# DLY-056.net
KiCad netlist of a schematic drawn in Altium Designer
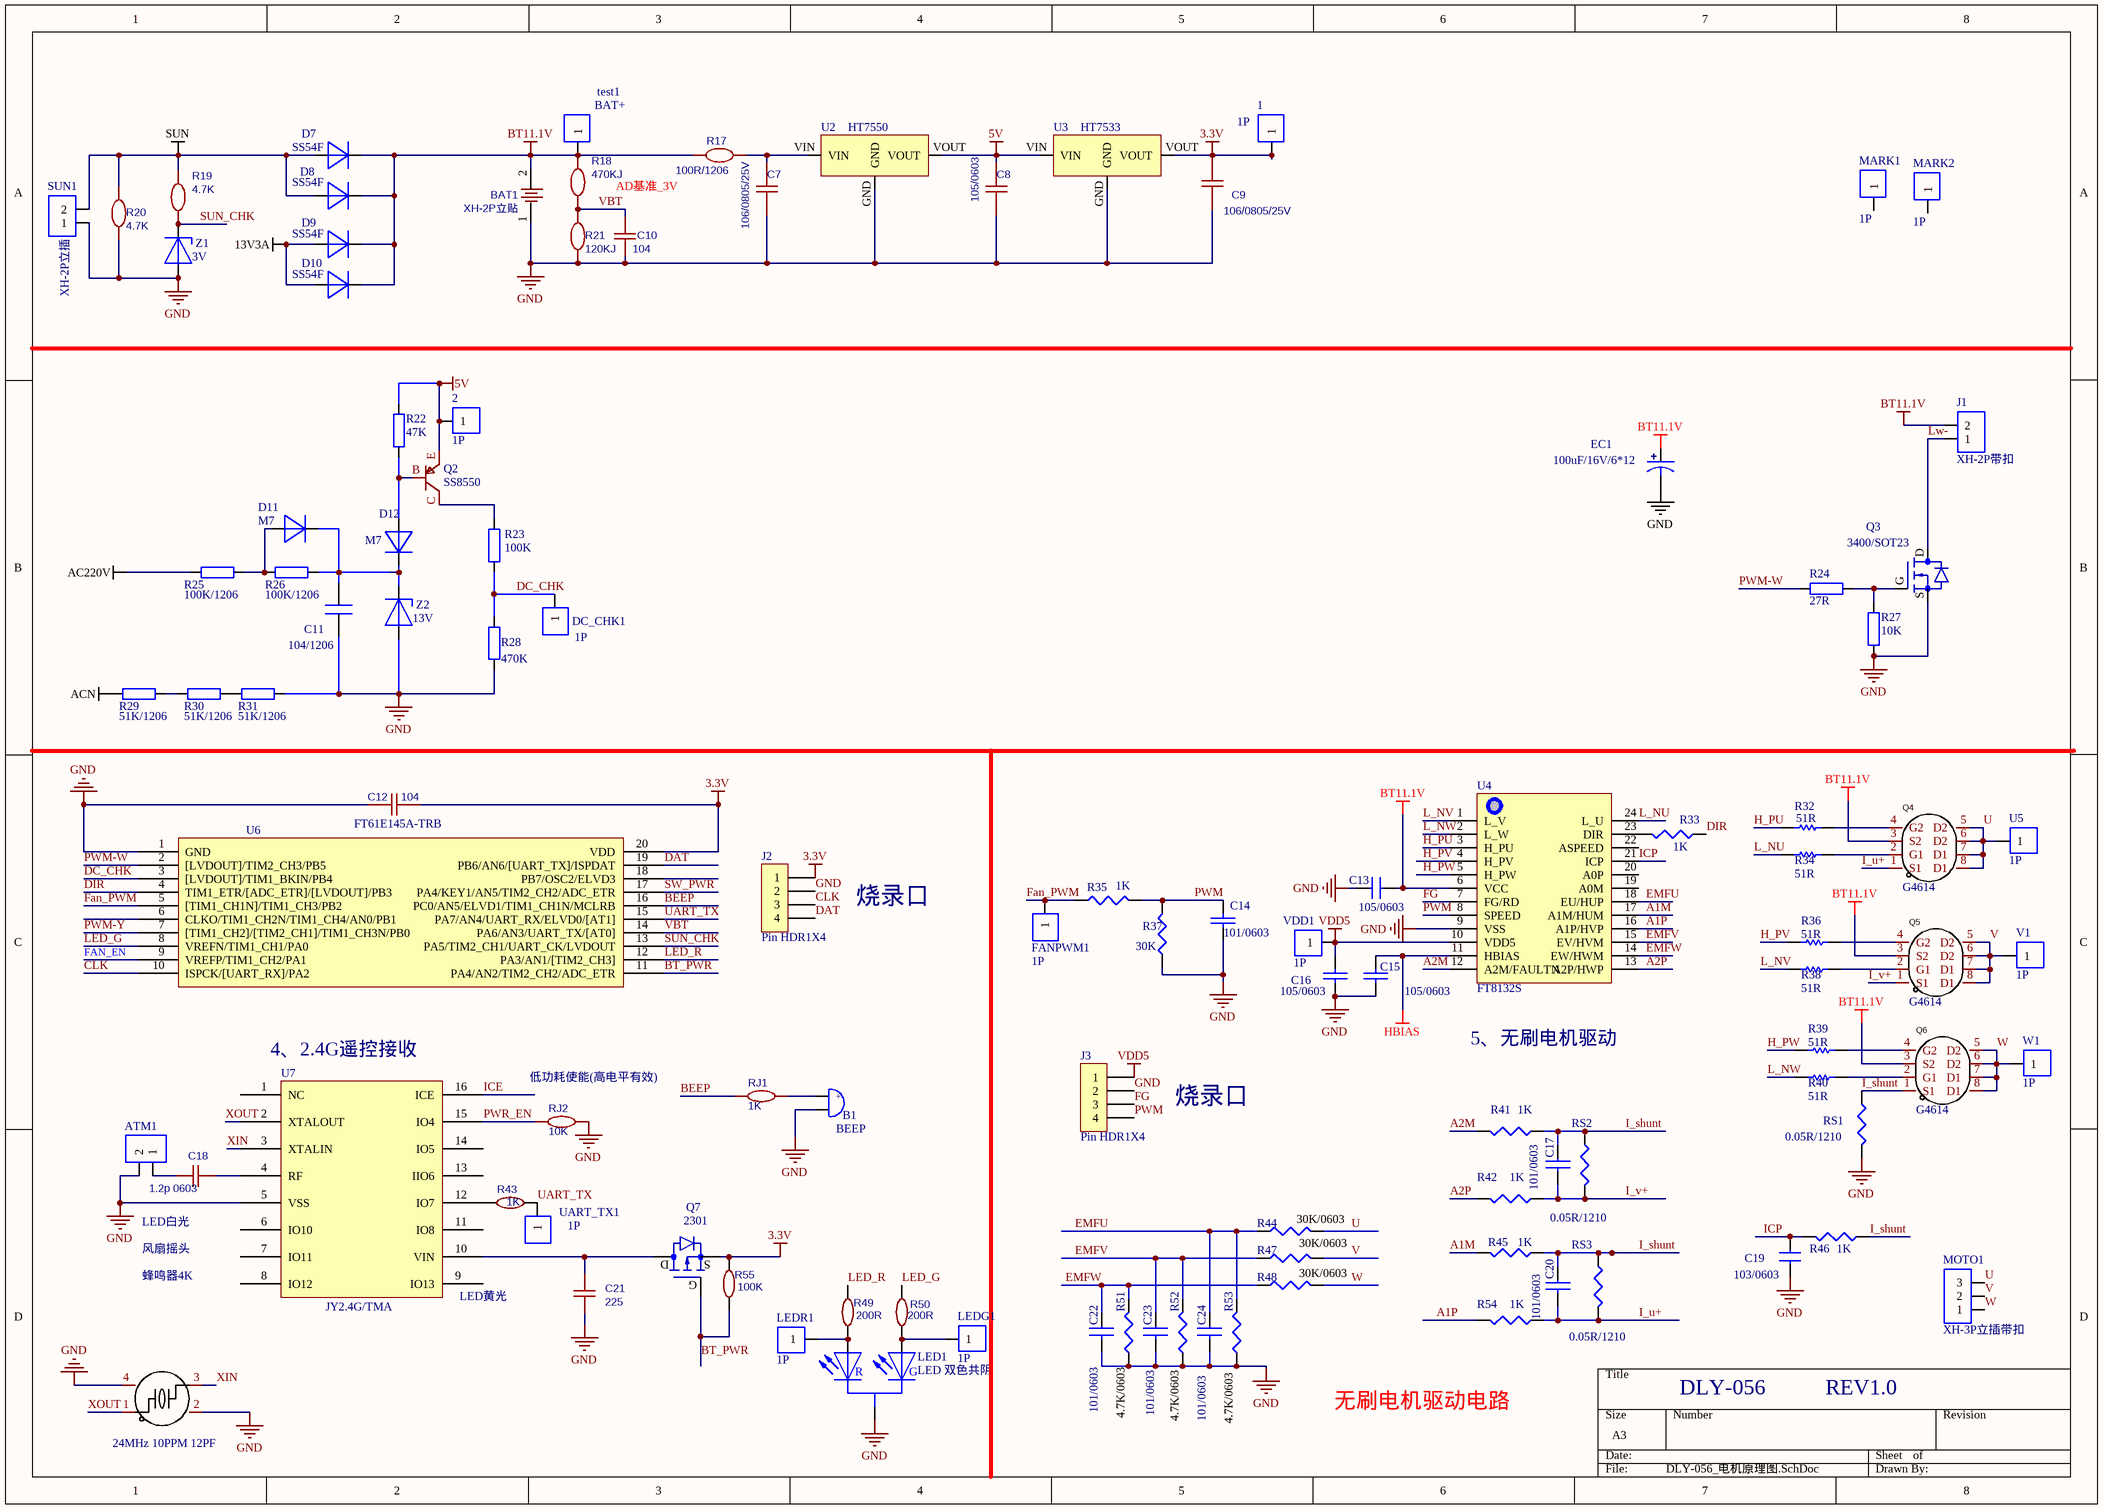
[diagram p0: DLY-056_电机原理图.SchDoc]

(export (version "E")
  (design (tool "Eeschema 10.0.6"))
  (components
    (comp (ref "1")
      (value "1P")
      (footprint "TEST3.0_top")
      (libsource (lib "KENNED 原理图标准封装-2023-9-7") (part "1P"))
    )
    (comp (ref "2")
      (value "1P")
      (footprint "TEST3.0_top")
      (libsource (lib "KENNED 原理图标准封装-2023-9-7") (part "1P"))
    )
    (comp (ref "ATM1")
      (value "2P")
      (footprint "SMT-ATN天线")
      (libsource (lib "KENNED 原理图标准封装-2023-9-7") (part "2P"))
    )
    (comp (ref "B1")
      (value "BEEP")
      (footprint "MI-蜂鸣器-1407")
      (description "蜂鸣器")
      (libsource (lib "蜂鸣器") (part "BEEP"))
    )
    (comp (ref "BAT1")
      (value "XH-2P立贴")
      (footprint "MI-VH2-2.5")
      (fields (field (name "BOM_MANUFACTURER PART") "CR1220-2") (field (name "BOM_SUPPLIER PART") "C70381"))
      (libsource (lib "altium-import") (part "root_3_12V_"))
    )
    (comp (ref "C7")
      (value "106/0805/25V")
      (footprint "0805_c")
      (fields (field (name "CONTRIBUTOR") "LCEDA_Lib"))
      (libsource (lib "altium-import") (part "root_3_0.1u_"))
    )
    (comp (ref "C8")
      (value "105/0603")
      (footprint "0603_c")
      (fields (field (name "CONTRIBUTOR") "LCEDA_Lib"))
      (libsource (lib "altium-import") (part "root_3_0.1u_"))
    )
    (comp (ref "C9")
      (value "106/0805/25V")
      (footprint "0603_c")
      (fields (field (name "CONTRIBUTOR") "LCEDA_Lib"))
      (libsource (lib "altium-import") (part "root_3_0.1u_"))
    )
    (comp (ref "C10")
      (value "104")
      (footprint "0603_C")
      (fields
        (field (name "BOM_SUPPLIER PART") "C295939")
        (field (name "BOM_MANUFACTURER PART") "0402X224J100CT")
        (field (name "CONTRIBUTOR") "LCSC")
      )
      (libsource (lib "altium-import") (part "root_0_100nF_"))
    )
    (comp (ref "C11")
      (value "104/1206")
      (footprint "1206_C")
      (libsource (lib "KENNED 原理图标准封装-20170515") (part "Cap"))
    )
    (comp (ref "C12")
      (value "104")
      (footprint "0603_C")
      (fields
        (field (name "BOM_MANUFACTURER PART") "CL10B104KA8NNNC")
        (field (name "BOM_SUPPLIER PART") "C1590")
      )
      (libsource (lib "altium-import") (part "root_2_102/400V_"))
    )
    (comp (ref "C13")
      (value "105/0603")
      (footprint "0603_C")
      (description "Capacitor")
      (libsource (lib "*") (part "CAP"))
    )
    (comp (ref "C14")
      (value "101/0603")
      (footprint "0603_C")
      (description "Capacitor")
      (libsource (lib "") (part "CAP_1"))
    )
    (comp (ref "C15")
      (value "105/0603")
      (footprint "0603_C")
      (description "Capacitor")
      (libsource (lib "*") (part "CAP-CC"))
    )
    (comp (ref "C16")
      (value "105/0603")
      (footprint "0603_C")
      (description "Capacitor")
      (libsource (lib "*") (part "CAP-CC"))
    )
    (comp (ref "C17") (value "101/0603") (footprint "0603_C") (libsource (lib "*") (part "CAP NP")))
    (comp (ref "C18")
      (value "1.2p 0603")
      (footprint "0603_C")
      (description "0603")
      (fields
        (field (name "BOM_SUPPLIER PART") "C295939")
        (field (name "BOM_MANUFACTURER PART") "0402X224J100CT")
        (field (name "CONTRIBUTOR") "LCSC")
      )
      (libsource (lib "altium-import") (part "root_3_100nF_"))
    )
    (comp (ref "C19")
      (value "103/0603")
      (footprint "0603_C")
      (description "Capacitor")
      (libsource (lib "*") (part "CAP"))
    )
    (comp (ref "C20") (value "101/0603") (footprint "0603_C") (libsource (lib "*") (part "CAP NP")))
    (comp (ref "C21")
      (value "225")
      (footprint "0603_C")
      (description "0603")
      (fields
        (field (name "BOM_SUPPLIER PART") "C295939")
        (field (name "BOM_MANUFACTURER PART") "0402X224J100CT")
        (field (name "CONTRIBUTOR") "LCSC")
      )
      (libsource (lib "altium-import") (part "root_2_100nF_"))
    )
    (comp (ref "C22") (value "101/0603") (footprint "0603_C") (libsource (lib "*") (part "CAP NP")))
    (comp (ref "C23") (value "101/0603") (footprint "0603_C") (libsource (lib "*") (part "CAP NP")))
    (comp (ref "C24") (value "101/0603") (footprint "0603_C") (libsource (lib "*") (part "CAP NP")))
    (comp (ref "D7")
      (value "SS54F")
      (footprint "SMT-SMA")
      (libsource (lib "KENNED 原理图标准封装-20170515") (part "Diode"))
    )
    (comp (ref "D8")
      (value "SS54F")
      (footprint "SMT-SMA")
      (libsource (lib "KENNED 原理图标准封装-20170515") (part "Diode"))
    )
    (comp (ref "D9")
      (value "SS54F")
      (footprint "SMT-SMA")
      (libsource (lib "KENNED 原理图标准封装-20170515") (part "Diode"))
    )
    (comp (ref "D10")
      (value "SS54F")
      (footprint "SMT-SMA")
      (libsource (lib "KENNED 原理图标准封装-20170515") (part "Diode"))
    )
    (comp (ref "D11")
      (value "M7")
      (footprint "SMT-SOD123锡膏")
      (libsource (lib "KENNED 原理图标准封装-20170515") (part "Diode"))
    )
    (comp (ref "D12")
      (value "M7")
      (footprint "SMT-SOD123锡膏")
      (libsource (lib "KENNED 原理图标准封装-20170515") (part "Diode"))
    )
    (comp (ref "DC_CHK1")
      (value "1P")
      (footprint "TEST3.0_top")
      (libsource (lib "KENNED 原理图标准封装-2023-9-7") (part "1P"))
    )
    (comp (ref "EC1")
      (value "100uF/16V/6*12")
      (footprint "DIP-EC2.5X6.3X11.2")
      (description "贴片电解电容")
      (libsource (lib "电容") (part "SMD_ECAP"))
    )
    (comp (ref "FANPWM1")
      (value "1P")
      (footprint "TEST3.0_top")
      (libsource (lib "KENNED 原理图标准封装-2023-9-7") (part "1P"))
    )
    (comp (ref "J1")
      (value "XH-2P带扣")
      (footprint "MI-VH2-2.5")
      (libsource (lib "KENNED 原理图标准封装-2023-9-7") (part "2P"))
    )
    (comp (ref "J2") (value "Pin HDR1X4") (footprint "烧录口") (libsource (lib "排针") (part "Pin HDR1X4")))
    (comp (ref "J3") (value "Pin HDR1X4") (footprint "烧录口") (libsource (lib "排针") (part "Pin HDR1X4")))
    (comp (ref "LED1")
      (value "LED 双色共阴")
      (footprint "PH2.0-3P")
      (libsource (lib "KENNED 原理图标准封装-2023-9-7") (part "LED 双色共阴"))
    )
    (comp (ref "LEDG1")
      (value "1P")
      (footprint "TEST3.0_top")
      (libsource (lib "KENNED 原理图标准封装-2023-9-7") (part "1P"))
    )
    (comp (ref "LEDR1")
      (value "1P")
      (footprint "TEST3.0_top")
      (libsource (lib "KENNED 原理图标准封装-2023-9-7") (part "1P"))
    )
    (comp (ref "MARK1")
      (value "1P")
      (footprint "SMT-MARK")
      (libsource (lib "KENNED 原理图标准封装-2023-9-7") (part "1P"))
    )
    (comp (ref "MARK2")
      (value "1P")
      (footprint "SMT-MARK")
      (libsource (lib "KENNED 原理图标准封装-2023-9-7") (part "1P"))
    )
    (comp (ref "MOTO1")
      (value "XH-3P立插带扣")
      (footprint "MI-VH3-2.5")
      (libsource (lib "KENNED 原理图标准封装-2023-9-7") (part "3P"))
    )
    (comp (ref "Q2")
      (value "SS8550")
      (footprint "SMT-三极管-SOT23锡膏")
      (libsource (lib "KENNED 原理图标准封装-2023-9-7") (part "PNP"))
    )
    (comp (ref "Q3")
      (value "3400/SOT23")
      (footprint "SMT-MOS管-SOT23锡膏")
      (libsource (lib "KENNED 原理图标准封装-2023-9-7") (part "N MOS"))
    )
    (comp (ref "Q4")
      (value "G4614")
      (footprint "SOIC-8_150mil")
      (libsource (lib "altium-import") (part "root_2_mirrored_G4614_"))
    )
    (comp (ref "Q5")
      (value "G4614")
      (footprint "SOIC-8_150mil")
      (libsource (lib "altium-import") (part "root_2_mirrored_G4614_"))
    )
    (comp (ref "Q6")
      (value "G4614")
      (footprint "SOIC-8_150mil")
      (libsource (lib "altium-import") (part "root_2_mirrored_G4614_"))
    )
    (comp (ref "Q7")
      (value "2301")
      (footprint "SMT-MOS管-SOT23锡膏")
      (libsource (lib "KENNED 原理图标准封装-2023-9-7") (part "P MOS"))
    )
    (comp (ref "R17")
      (value "100R/1206")
      (footprint "SMT-1206r")
      (fields (field (name "CONTRIBUTOR") "LCEDA_Lib"))
      (libsource (lib "altium-import") (part "root_2_1k_"))
    )
    (comp (ref "R18")
      (value "470KJ")
      (footprint "0603_R")
      (fields (field (name "CONTRIBUTOR") "LCEDA_Lib"))
      (libsource (lib "altium-import") (part "root_1_1k_"))
    )
    (comp (ref "R19")
      (value "4.7K")
      (footprint "0603_R")
      (fields (field (name "CONTRIBUTOR") "LCEDA_Lib"))
      (libsource (lib "altium-import") (part "root_1_1k_"))
    )
    (comp (ref "R20")
      (value "4.7K")
      (footprint "0603_R")
      (fields (field (name "CONTRIBUTOR") "LCEDA_Lib"))
      (libsource (lib "altium-import") (part "root_1_1k_"))
    )
    (comp (ref "R21")
      (value "120KJ")
      (footprint "0603_R")
      (fields (field (name "CONTRIBUTOR") "LCEDA_Lib"))
      (libsource (lib "altium-import") (part "root_1_1k_"))
    )
    (comp (ref "R22")
      (value "47K")
      (footprint "SMT-0603R")
      (libsource (lib "KENNED 原理图标准封装-20170515") (part "Res"))
    )
    (comp (ref "R23")
      (value "100K")
      (footprint "SMT-0603R")
      (libsource (lib "KENNED 原理图标准封装-20170515") (part "Res"))
    )
    (comp (ref "R24") (value "27R") (footprint "SMT-0603R") (libsource (lib "*") (part "Res")))
    (comp (ref "R25")
      (value "100K/1206")
      (footprint "SMT-1206")
      (libsource (lib "KENNED 原理图标准封装-20170515") (part "Res"))
    )
    (comp (ref "R26")
      (value "100K/1206")
      (footprint "SMT-1206")
      (libsource (lib "KENNED 原理图标准封装-20170515") (part "Res"))
    )
    (comp (ref "R27") (value "10K") (footprint "SMT-0603R") (libsource (lib "*") (part "Res")))
    (comp (ref "R28")
      (value "470K")
      (footprint "SMT-0603R")
      (libsource (lib "KENNED 原理图标准封装-20170515") (part "Res"))
    )
    (comp (ref "R29")
      (value "51K/1206")
      (footprint "SMT-1206")
      (libsource (lib "KENNED 原理图标准封装-20170515") (part "Res"))
    )
    (comp (ref "R30")
      (value "51K/1206")
      (footprint "SMT-1206")
      (libsource (lib "KENNED 原理图标准封装-20170515") (part "Res"))
    )
    (comp (ref "R31")
      (value "51K/1206")
      (footprint "SMT-1206")
      (libsource (lib "KENNED 原理图标准封装-20170515") (part "Res"))
    )
    (comp (ref "R32") (value "51R") (footprint "SMT-0603R") (libsource (lib "*") (part "RES")))
    (comp (ref "R33") (value "1K") (footprint "SMT-0603R") (libsource (lib "*") (part "RES(SMD)")))
    (comp (ref "R34") (value "51R") (footprint "SMT-0603R") (libsource (lib "*") (part "RES")))
    (comp (ref "R35") (value "1K") (footprint "SMT-0603R") (libsource (lib "*") (part "RES(SMD)")))
    (comp (ref "R36") (value "51R") (footprint "SMT-0603R") (libsource (lib "*") (part "RES")))
    (comp (ref "R37") (value "30K") (footprint "SMT-0603R") (libsource (lib "*") (part "RES(SMD)")))
    (comp (ref "R38") (value "51R") (footprint "SMT-0603R") (libsource (lib "*") (part "RES")))
    (comp (ref "R39") (value "51R") (footprint "SMT-0603R") (libsource (lib "*") (part "RES")))
    (comp (ref "R40") (value "51R") (footprint "SMT-0603R") (libsource (lib "*") (part "RES")))
    (comp (ref "R41") (value "1K") (footprint "SMT-0603R") (libsource (lib "*") (part "RES(SMD)")))
    (comp (ref "R42") (value "1K") (footprint "SMT-0603R") (libsource (lib "*") (part "RES(SMD)")))
    (comp (ref "R43")
      (value "1K")
      (footprint "SMT-0603R")
      (fields
        (field (name "BOM_MANUFACTURER PART") "0402WGJ0165TCE")
        (field (name "BOM_SUPPLIER PART") "C57065")
      )
      (libsource (lib "altium-import") (part "root_2_51K_"))
    )
    (comp (ref "R44") (value "30K/0603") (footprint "SMT-0603R") (libsource (lib "") (part "RES(SMD)_1")))
    (comp (ref "R45") (value "1K") (footprint "SMT-0603R") (libsource (lib "*") (part "RES(SMD)")))
    (comp (ref "R46") (value "1K") (footprint "SMT-0603R") (libsource (lib "*") (part "RES(SMD)")))
    (comp (ref "R47") (value "30K/0603") (footprint "SMT-0603R") (libsource (lib "") (part "RES(SMD)_1")))
    (comp (ref "R48") (value "30K/0603") (footprint "SMT-0603R") (libsource (lib "") (part "RES(SMD)_1")))
    (comp (ref "R49")
      (value "200R")
      (footprint "SMT-0603R")
      (fields
        (field (name "BOM_MANUFACTURER PART") "0402WGJ0165TCE")
        (field (name "BOM_SUPPLIER PART") "C57065")
      )
      (libsource (lib "altium-import") (part "root_3_51K_"))
    )
    (comp (ref "R50")
      (value "200R")
      (footprint "SMT-0603R")
      (fields
        (field (name "BOM_MANUFACTURER PART") "0402WGJ0165TCE")
        (field (name "BOM_SUPPLIER PART") "C57065")
      )
      (libsource (lib "altium-import") (part "root_3_51K_"))
    )
    (comp (ref "R51") (value "4.7K/0603") (footprint "SMT-0603R") (libsource (lib "") (part "RES(SMD)_1")))
    (comp (ref "R52") (value "4.7K/0603") (footprint "SMT-0603R") (libsource (lib "") (part "RES(SMD)_1")))
    (comp (ref "R53") (value "4.7K/0603") (footprint "SMT-0603R") (libsource (lib "") (part "RES(SMD)_1")))
    (comp (ref "R54") (value "1K") (footprint "SMT-0603R") (libsource (lib "*") (part "RES(SMD)")))
    (comp (ref "R55")
      (value "100K")
      (footprint "SMT-0603R")
      (fields
        (field (name "BOM_MANUFACTURER PART") "0402WGJ0165TCE")
        (field (name "BOM_SUPPLIER PART") "C57065")
      )
      (libsource (lib "altium-import") (part "root_3_51K_"))
    )
    (comp (ref "RJ1")
      (value "1K")
      (footprint "SMT-0603R")
      (fields
        (field (name "BOM_SUPPLIER PART") "C270129")
        (field (name "BOM_MANUFACTURER PART") "RMC04024.7K1%N")
        (field (name "CONTRIBUTOR") "LCSC")
      )
      (libsource (lib "altium-import") (part "root_0_300K_"))
    )
    (comp (ref "RJ2")
      (value "10K")
      (footprint "SMT-0603R")
      (fields
        (field (name "BOM_SUPPLIER PART") "C270129")
        (field (name "BOM_MANUFACTURER PART") "RMC04024.7K1%N")
        (field (name "CONTRIBUTOR") "LCSC")
      )
      (libsource (lib "altium-import") (part "root_2_300K_"))
    )
    (comp (ref "RS1") (value "0.05R/1210") (footprint "SMT-1210") (libsource (lib "") (part "RES(SMD)_1")))
    (comp (ref "RS2") (value "0.05R/1210") (footprint "SMT-1210") (libsource (lib "") (part "RES(SMD)_1")))
    (comp (ref "RS3") (value "0.05R/1210") (footprint "SMT-1210") (libsource (lib "") (part "RES(SMD)_1")))
    (comp (ref "SUN1")
      (value "XH-2P立插")
      (footprint "MI-VH2-2.5")
      (libsource (lib "KENNED 原理图标准封装-2023-9-7") (part "2P"))
    )
    (comp (ref "test1")
      (value "BAT+")
      (footprint "test3.0_top")
      (libsource (lib "KENNED 原理图标准封装-2023-9-7") (part "1P"))
    )
    (comp (ref "U2")
      (value "HT7550")
      (footprint "SMT-LDO-SOT23锡膏")
      (libsource (lib "KENNED 原理图标准封装-2023-9-7") (part "IC HT7550"))
    )
    (comp (ref "U3")
      (value "HT7533")
      (footprint "SMT-LDO-SOT23锡膏")
      (libsource (lib "KENNED 原理图标准封装-2023-9-7") (part "IC HT7550"))
    )
    (comp (ref "U4")
      (value "FT8132S")
      (footprint "TSSOP-24")
      (description "FT8131Q SSOP24")
      (libsource (lib "FT8132S-24V-MODE_V1.2") (part "FT8131S"))
    )
    (comp (ref "U5")
      (value "1P")
      (footprint "TEST3.0_top")
      (libsource (lib "KENNED 原理图标准封装-2023-9-7") (part "1P"))
    )
    (comp (ref "U6")
      (value "FT61E145A-TRB")
      (footprint "TSSOP-20")
      (libsource (lib "FT61F145A") (part "FT61F145A-RB"))
    )
    (comp (ref "U7")
      (value "JY2.4G/TMA")
      (footprint "SOIC-16_150mil")
      (description "SOP16")
      (libsource (lib "JY2.4G_TMA") (part "Component_1"))
    )
    (comp (ref "UART_TX1")
      (value "1P")
      (footprint "TEST3.0_top")
      (libsource (lib "KENNED 原理图标准封装-2023-9-7") (part "1P"))
    )
    (comp (ref "V1")
      (value "1P")
      (footprint "TEST3.0_top")
      (libsource (lib "KENNED 原理图标准封装-2023-9-7") (part "1P"))
    )
    (comp (ref "VDD1")
      (value "1P")
      (footprint "TEST3.0_top")
      (libsource (lib "KENNED 原理图标准封装-2023-9-7") (part "1P"))
    )
    (comp (ref "W1")
      (value "1P")
      (footprint "TEST3.0_top")
      (libsource (lib "KENNED 原理图标准封装-2023-9-7") (part "1P"))
    )
    (comp (ref "X1")
      (value "X32258MOB4SI")
      (footprint "OSC 3225-4P")
      (description "24MHz 10PPM 12PF")
      (fields (field (name "MANUFACTURER") "YXC(扬兴晶振)"))
      (libsource (lib "altium-import") (part "root_0_X32258MOB4SI_"))
    )
    (comp (ref "Z1")
      (value "3V")
      (footprint "SMT-SOD123锡膏")
      (libsource (lib "KENNED 原理图标准封装-20170515") (part "Diode Z"))
    )
    (comp (ref "Z2")
      (value "13V")
      (footprint "SMT-SOD123锡膏")
      (libsource (lib "KENNED 原理图标准封装-20170515") (part "Diode Z"))
    )
  )
  (nets
    (net (code "1") (name "/A1M") (class "Default")
      (node (ref "R45") (pin "2") (pinfunction "2_2") (pintype "passive"))
      (node (ref "U4") (pin "17") (pinfunction "A1M/HUM_17") (pintype "passive"))
    )
    (net (code "2") (name "/A1P") (class "Default")
      (node (ref "R54") (pin "2") (pinfunction "2_2") (pintype "passive"))
      (node (ref "U4") (pin "16") (pinfunction "A1P/HVP_16") (pintype "passive"))
    )
    (net (code "3") (name "/A2M") (class "Default")
      (node (ref "R41") (pin "2") (pinfunction "2_2") (pintype "passive"))
      (node (ref "U4") (pin "12") (pinfunction "A2M/FAULTN_12") (pintype "passive"))
    )
    (net (code "4") (name "/A2P") (class "Default")
      (node (ref "R42") (pin "2") (pinfunction "2_2") (pintype "passive"))
      (node (ref "U4") (pin "13") (pinfunction "A2P/HWP_13") (pintype "passive"))
    )
    (net (code "5") (name "/BEEP") (class "Default")
      (node (ref "RJ1") (pin "1") (pinfunction "1_1") (pintype "passive"))
      (node (ref "U6") (pin "16") (pinfunction "PC0/AN5/ELVD1/TIM1_CH1N/MCLRB_16") (pintype "passive"))
    )
    (net (code "6") (name "/BT_PWR") (class "Default")
      (node (ref "Q7") (pin "G") (pinfunction "G_G") (pintype "passive"))
      (node (ref "R55") (pin "2") (pinfunction "2_2") (pintype "passive"))
      (node (ref "U6") (pin "11") (pinfunction "PA4/AN2/TIM2_CH2/ADC_ETR_11") (pintype "passive"))
    )
    (net (code "7") (name "/CLK") (class "Default")
      (node (ref "J2") (pin "3") (pinfunction "3_3") (pintype "passive"))
      (node (ref "U6") (pin "10") (pinfunction "ISPCK/[UART_RX]/PA2_10") (pintype "passive"))
    )
    (net (code "8") (name "/DAT") (class "Default")
      (node (ref "J2") (pin "4") (pinfunction "4_4") (pintype "passive"))
      (node (ref "U6") (pin "19") (pinfunction "PB6/AN6/[UART_TX]/ISPDAT_19") (pintype "passive"))
    )
    (net (code "9") (name "/DC_CHK") (class "Default")
      (node (ref "DC_CHK1") (pin "1") (pinfunction "1_1") (pintype "passive"))
      (node (ref "R23") (pin "1") (pinfunction "1_1") (pintype "passive"))
      (node (ref "R28") (pin "1") (pinfunction "1_1") (pintype "passive"))
      (node (ref "U6") (pin "3") (pinfunction "[LVDOUT]/TIM1_BKIN/PB4_3") (pintype "passive"))
    )
    (net (code "10") (name "/DIR") (class "Default")
      (node (ref "R33") (pin "1") (pinfunction "1_1") (pintype "passive"))
      (node (ref "U6") (pin "4") (pinfunction "TIM1_ETR/[ADC_ETR]/[LVDOUT]/PB3_4") (pintype "passive"))
    )
    (net (code "11") (name "/EMFU") (class "Default")
      (node (ref "C24") (pin "1") (pinfunction "1_1") (pintype "passive"))
      (node (ref "R44") (pin "1") (pinfunction "1_1") (pintype "passive"))
      (node (ref "R53") (pin "2") (pinfunction "2_2") (pintype "passive"))
      (node (ref "U4") (pin "18") (pinfunction "EU/HUP_18") (pintype "passive"))
    )
    (net (code "12") (name "/EMFV") (class "Default")
      (node (ref "C23") (pin "1") (pinfunction "1_1") (pintype "passive"))
      (node (ref "R47") (pin "1") (pinfunction "1_1") (pintype "passive"))
      (node (ref "R52") (pin "2") (pinfunction "2_2") (pintype "passive"))
      (node (ref "U4") (pin "15") (pinfunction "EV/HVM_15") (pintype "passive"))
    )
    (net (code "13") (name "/EMFW") (class "Default")
      (node (ref "C22") (pin "1") (pinfunction "1_1") (pintype "passive"))
      (node (ref "R48") (pin "1") (pinfunction "1_1") (pintype "passive"))
      (node (ref "R51") (pin "2") (pinfunction "2_2") (pintype "passive"))
      (node (ref "U4") (pin "14") (pinfunction "EW/HWM_14") (pintype "passive"))
    )
    (net (code "14") (name "/FAN_EN") (class "Default")
      (node (ref "U6") (pin "9") (pinfunction "VREFP/TIM1_CH2/PA1_9") (pintype "passive"))
    )
    (net (code "15") (name "/FG") (class "Default")
      (node (ref "J3") (pin "3") (pinfunction "3_3") (pintype "passive"))
      (node (ref "U4") (pin "7") (pinfunction "FG/RD_7") (pintype "passive"))
    )
    (net (code "16") (name "/Fan_PWM") (class "Default")
      (node (ref "FANPWM1") (pin "1") (pinfunction "1_1") (pintype "passive"))
      (node (ref "R35") (pin "1") (pinfunction "1_1") (pintype "passive"))
      (node (ref "U6") (pin "5") (pinfunction "[TIM1_CH1N]/TIM1_CH3/PB2_5") (pintype "passive"))
    )
    (net (code "17") (name "/H_PU") (class "Default")
      (node (ref "R32") (pin "1") (pinfunction "1_1") (pintype "passive"))
      (node (ref "U4") (pin "3") (pinfunction "H_PU_3") (pintype "passive"))
    )
    (net (code "18") (name "/H_PV") (class "Default")
      (node (ref "R36") (pin "1") (pinfunction "1_1") (pintype "passive"))
      (node (ref "U4") (pin "4") (pinfunction "H_PV_4") (pintype "passive"))
    )
    (net (code "19") (name "/H_PW") (class "Default")
      (node (ref "R39") (pin "1") (pinfunction "1_1") (pintype "passive"))
      (node (ref "U4") (pin "5") (pinfunction "H_PW_5") (pintype "passive"))
    )
    (net (code "20") (name "/ICE") (class "Default")
      (node (ref "U7") (pin "16") (pinfunction "ICE_16") (pintype "passive"))
    )
    (net (code "21") (name "/ICP") (class "Default")
      (node (ref "C19") (pin "1") (pinfunction "1_1") (pintype "passive"))
      (node (ref "R46") (pin "2") (pinfunction "2_2") (pintype "passive"))
      (node (ref "U4") (pin "21") (pinfunction "ICP_21") (pintype "passive"))
    )
    (net (code "22") (name "/I_shunt") (class "Default")
      (node (ref "C17") (pin "1") (pinfunction "1_1") (pintype "passive"))
      (node (ref "C20") (pin "1") (pinfunction "1_1") (pintype "passive"))
      (node (ref "Q6") (pin "1") (pinfunction "S1_1") (pintype "passive"))
      (node (ref "R41") (pin "1") (pinfunction "1_1") (pintype "passive"))
      (node (ref "R45") (pin "1") (pinfunction "1_1") (pintype "passive"))
      (node (ref "R46") (pin "1") (pinfunction "1_1") (pintype "passive"))
      (node (ref "RS1") (pin "1") (pinfunction "1_1") (pintype "passive"))
      (node (ref "RS2") (pin "1") (pinfunction "1_1") (pintype "passive"))
      (node (ref "RS3") (pin "1") (pinfunction "1_1") (pintype "passive"))
    )
    (net (code "23") (name "/I_u+") (class "Default")
      (node (ref "C20") (pin "2") (pinfunction "2_2") (pintype "passive"))
      (node (ref "Q4") (pin "1") (pinfunction "S1_1") (pintype "passive"))
      (node (ref "R54") (pin "1") (pinfunction "1_1") (pintype "passive"))
      (node (ref "RS3") (pin "2") (pinfunction "2_2") (pintype "passive"))
    )
    (net (code "24") (name "/I_v+") (class "Default")
      (node (ref "C17") (pin "2") (pinfunction "2_2") (pintype "passive"))
      (node (ref "Q5") (pin "1") (pinfunction "S1_1") (pintype "passive"))
      (node (ref "R42") (pin "1") (pinfunction "1_1") (pintype "passive"))
      (node (ref "RS2") (pin "2") (pinfunction "2_2") (pintype "passive"))
    )
    (net (code "25") (name "/LED_G") (class "Default")
      (node (ref "R50") (pin "1") (pinfunction "1_1") (pintype "passive"))
      (node (ref "U6") (pin "8") (pinfunction "VREFN/TIM1_CH1/PA0_8") (pintype "passive"))
    )
    (net (code "26") (name "/LED_R") (class "Default")
      (node (ref "R49") (pin "1") (pinfunction "1_1") (pintype "passive"))
      (node (ref "U6") (pin "12") (pinfunction "PA3/AN1/[TIM2_CH3]_12") (pintype "passive"))
    )
    (net (code "27") (name "/L_NU") (class "Default")
      (node (ref "R34") (pin "1") (pinfunction "1_1") (pintype "passive"))
      (node (ref "U4") (pin "24") (pinfunction "L_U_24") (pintype "passive"))
    )
    (net (code "28") (name "/L_NV") (class "Default")
      (node (ref "R38") (pin "1") (pinfunction "1_1") (pintype "passive"))
      (node (ref "U4") (pin "1") (pinfunction "L_V_1") (pintype "passive"))
    )
    (net (code "29") (name "/L_NW") (class "Default")
      (node (ref "R40") (pin "1") (pinfunction "1_1") (pintype "passive"))
      (node (ref "U4") (pin "2") (pinfunction "L_W_2") (pintype "passive"))
    )
    (net (code "30") (name "/Lw-") (class "Default")
      (node (ref "J1") (pin "1") (pinfunction "1_1") (pintype "passive"))
      (node (ref "Q3") (pin "D") (pinfunction "D_D") (pintype "passive"))
    )
    (net (code "31") (name "/PWM") (class "Default")
      (node (ref "C14") (pin "1") (pinfunction "1_1") (pintype "passive"))
      (node (ref "J3") (pin "4") (pinfunction "4_4") (pintype "passive"))
      (node (ref "R35") (pin "2") (pinfunction "2_2") (pintype "passive"))
      (node (ref "R37") (pin "2") (pinfunction "2_2") (pintype "passive"))
      (node (ref "U4") (pin "8") (pinfunction "SPEED_8") (pintype "passive"))
    )
    (net (code "32") (name "/PWM-W") (class "Default")
      (node (ref "R24") (pin "1") (pinfunction "1_1") (pintype "passive"))
      (node (ref "U6") (pin "2") (pinfunction "[LVDOUT]/TIM2_CH3/PB5_2") (pintype "passive"))
    )
    (net (code "33") (name "/PWM-Y") (class "Default")
      (node (ref "U6") (pin "7") (pinfunction "[TIM1_CH2]/[TIM2_CH1]/TIM1_CH3N/PB0_7") (pintype "passive"))
    )
    (net (code "34") (name "/PWR_EN") (class "Default")
      (node (ref "RJ2") (pin "2") (pinfunction "2_2") (pintype "passive"))
      (node (ref "U7") (pin "15") (pinfunction "IO4_15") (pintype "passive"))
    )
    (net (code "35") (name "/SUN_CHK") (class "Default")
      (node (ref "R19") (pin "1") (pinfunction "1_1") (pintype "passive"))
      (node (ref "U6") (pin "13") (pinfunction "PA5/TIM2_CH1/UART_CK/LVDOUT_13") (pintype "passive"))
      (node (ref "Z1") (pin "2") (pinfunction "2_2") (pintype "passive"))
    )
    (net (code "36") (name "/SW_PWR") (class "Default")
      (node (ref "U6") (pin "17") (pinfunction "PA4/KEY1/AN5/TIM2_CH2/ADC_ETR_17") (pintype "passive"))
    )
    (net (code "37") (name "/U") (class "Default")
      (node (ref "MOTO1") (pin "3") (pinfunction "3_3") (pintype "passive"))
      (node (ref "Q4") (pin "5") (pinfunction "D2_5") (pintype "passive"))
      (node (ref "Q4") (pin "6") (pinfunction "D2_6") (pintype "passive"))
      (node (ref "Q4") (pin "7") (pinfunction "D1_7") (pintype "passive"))
      (node (ref "Q4") (pin "8") (pinfunction "D1_8") (pintype "passive"))
      (node (ref "R44") (pin "2") (pinfunction "2_2") (pintype "passive"))
      (node (ref "U5") (pin "1") (pinfunction "1_1") (pintype "passive"))
    )
    (net (code "38") (name "/UART_TX") (class "Default")
      (node (ref "R43") (pin "1") (pinfunction "1_1") (pintype "passive"))
      (node (ref "U6") (pin "15") (pinfunction "PA7/AN4/UART_RX/ELVD0/[AT1]_15") (pintype "passive"))
      (node (ref "UART_TX1") (pin "1") (pinfunction "1_1") (pintype "passive"))
    )
    (net (code "39") (name "/V") (class "Default")
      (node (ref "MOTO1") (pin "2") (pinfunction "2_2") (pintype "passive"))
      (node (ref "Q5") (pin "5") (pinfunction "D2_5") (pintype "passive"))
      (node (ref "Q5") (pin "6") (pinfunction "D2_6") (pintype "passive"))
      (node (ref "Q5") (pin "7") (pinfunction "D1_7") (pintype "passive"))
      (node (ref "Q5") (pin "8") (pinfunction "D1_8") (pintype "passive"))
      (node (ref "R47") (pin "2") (pinfunction "2_2") (pintype "passive"))
      (node (ref "V1") (pin "1") (pinfunction "1_1") (pintype "passive"))
    )
    (net (code "40") (name "/VBT") (class "Default")
      (node (ref "C10") (pin "1") (pinfunction "1_1") (pintype "passive"))
      (node (ref "R18") (pin "1") (pinfunction "1_1") (pintype "passive"))
      (node (ref "R21") (pin "2") (pinfunction "2_2") (pintype "passive"))
      (node (ref "U6") (pin "14") (pinfunction "PA6/AN3/UART_TX/[AT0]_14") (pintype "passive"))
    )
    (net (code "41") (name "/W") (class "Default")
      (node (ref "MOTO1") (pin "1") (pinfunction "1_1") (pintype "passive"))
      (node (ref "Q6") (pin "5") (pinfunction "D2_5") (pintype "passive"))
      (node (ref "Q6") (pin "6") (pinfunction "D2_6") (pintype "passive"))
      (node (ref "Q6") (pin "7") (pinfunction "D1_7") (pintype "passive"))
      (node (ref "Q6") (pin "8") (pinfunction "D1_8") (pintype "passive"))
      (node (ref "R48") (pin "2") (pinfunction "2_2") (pintype "passive"))
      (node (ref "W1") (pin "1") (pinfunction "1_1") (pintype "passive"))
    )
    (net (code "42") (name "/XIN") (class "Default")
      (node (ref "U7") (pin "3") (pinfunction "XTALIN_3") (pintype "passive"))
      (node (ref "X1") (pin "3") (pinfunction "XOUT_3") (pintype "passive"))
    )
    (net (code "43") (name "/XOUT") (class "Default")
      (node (ref "U7") (pin "2") (pinfunction "XTALOUT_2") (pintype "passive"))
      (node (ref "X1") (pin "1") (pinfunction "XIN_1") (pintype "passive"))
    )
    (net (code "44") (name "3.3V") (class "Default")
      (node (ref "1") (pin "1") (pinfunction "1_1") (pintype "passive"))
      (node (ref "C12") (pin "1") (pinfunction "1_1") (pintype "passive"))
      (node (ref "C9") (pin "1") (pinfunction "1_1") (pintype "passive"))
      (node (ref "J2") (pin "1") (pinfunction "1_1") (pintype "passive"))
      (node (ref "Q7") (pin "S") (pinfunction "S_S") (pintype "passive"))
      (node (ref "R55") (pin "1") (pinfunction "1_1") (pintype "passive"))
      (node (ref "U3") (pin "VOUT") (pinfunction "VOUT_VOUT") (pintype "passive"))
      (node (ref "U6") (pin "20") (pinfunction "VDD_20") (pintype "passive"))
    )
    (net (code "45") (name "5V") (class "Default")
      (node (ref "2") (pin "1") (pinfunction "1_1") (pintype "passive"))
      (node (ref "C8") (pin "1") (pinfunction "1_1") (pintype "passive"))
      (node (ref "Q2") (pin "E") (pinfunction "E_E") (pintype "passive"))
      (node (ref "R22") (pin "2") (pinfunction "2_2") (pintype "passive"))
      (node (ref "U2") (pin "VOUT") (pinfunction "VOUT_VOUT") (pintype "passive"))
      (node (ref "U3") (pin "VIN") (pinfunction "VIN_VIN") (pintype "passive"))
    )
    (net (code "46") (name "13V3A") (class "Default")
      (node (ref "D10") (pin "1") (pinfunction "1_1") (pintype "passive"))
      (node (ref "D9") (pin "1") (pinfunction "1_1") (pintype "passive"))
    )
    (net (code "47") (name "AC220V") (class "Default")
      (node (ref "R25") (pin "1") (pinfunction "1_1") (pintype "passive"))
    )
    (net (code "48") (name "ACN") (class "Default")
      (node (ref "R29") (pin "1") (pinfunction "1_1") (pintype "passive"))
    )
    (net (code "49") (name "BT11.1V") (class "Default")
      (node (ref "BAT1") (pin "2") (pinfunction "1_2") (pintype "passive"))
      (node (ref "C13") (pin "2") (pinfunction "2_2") (pintype "passive"))
      (node (ref "D10") (pin "2") (pinfunction "2_2") (pintype "passive"))
      (node (ref "D7") (pin "2") (pinfunction "2_2") (pintype "passive"))
      (node (ref "D8") (pin "2") (pinfunction "2_2") (pintype "passive"))
      (node (ref "D9") (pin "2") (pinfunction "2_2") (pintype "passive"))
      (node (ref "EC1") (pin "1") (pinfunction "1_1") (pintype "passive"))
      (node (ref "J1") (pin "2") (pinfunction "2_2") (pintype "passive"))
      (node (ref "Q4") (pin "3") (pinfunction "S2_3") (pintype "passive"))
      (node (ref "Q5") (pin "3") (pinfunction "S2_3") (pintype "passive"))
      (node (ref "Q6") (pin "3") (pinfunction "S2_3") (pintype "passive"))
      (node (ref "R17") (pin "2") (pinfunction "2_2") (pintype "passive"))
      (node (ref "R18") (pin "2") (pinfunction "2_2") (pintype "passive"))
      (node (ref "U4") (pin "6") (pinfunction "VCC_6") (pintype "passive"))
      (node (ref "test1") (pin "1") (pinfunction "1_1") (pintype "passive"))
    )
    (net (code "50") (name "GND") (class "Default")
      (node (ref "ATM1") (pin "2") (pinfunction "2_2") (pintype "passive"))
      (node (ref "B1") (pin "2") (pinfunction "2_2") (pintype "passive"))
      (node (ref "BAT1") (pin "1") (pinfunction "2_1") (pintype "passive"))
      (node (ref "C10") (pin "2") (pinfunction "2_2") (pintype "passive"))
      (node (ref "C11") (pin "1") (pinfunction "1_1") (pintype "passive"))
      (node (ref "C12") (pin "2") (pinfunction "2_2") (pintype "passive"))
      (node (ref "C13") (pin "1") (pinfunction "1_1") (pintype "passive"))
      (node (ref "C14") (pin "2") (pinfunction "2_2") (pintype "passive"))
      (node (ref "C15") (pin "1") (pinfunction "1_1") (pintype "passive"))
      (node (ref "C16") (pin "1") (pinfunction "1_1") (pintype "passive"))
      (node (ref "C19") (pin "2") (pinfunction "2_2") (pintype "passive"))
      (node (ref "C21") (pin "1") (pinfunction "1_1") (pintype "passive"))
      (node (ref "C22") (pin "2") (pinfunction "2_2") (pintype "passive"))
      (node (ref "C23") (pin "2") (pinfunction "2_2") (pintype "passive"))
      (node (ref "C24") (pin "2") (pinfunction "2_2") (pintype "passive"))
      (node (ref "C7") (pin "2") (pinfunction "2_2") (pintype "passive"))
      (node (ref "C8") (pin "2") (pinfunction "2_2") (pintype "passive"))
      (node (ref "C9") (pin "2") (pinfunction "2_2") (pintype "passive"))
      (node (ref "EC1") (pin "2") (pinfunction "2_2") (pintype "passive"))
      (node (ref "J2") (pin "2") (pinfunction "2_2") (pintype "passive"))
      (node (ref "J3") (pin "2") (pinfunction "2_2") (pintype "passive"))
      (node (ref "LED1") (pin "2") (pinfunction "2_2") (pintype "passive"))
      (node (ref "Q3") (pin "S") (pinfunction "S_S") (pintype "passive"))
      (node (ref "R20") (pin "1") (pinfunction "1_1") (pintype "passive"))
      (node (ref "R21") (pin "1") (pinfunction "1_1") (pintype "passive"))
      (node (ref "R27") (pin "1") (pinfunction "1_1") (pintype "passive"))
      (node (ref "R28") (pin "2") (pinfunction "2_2") (pintype "passive"))
      (node (ref "R31") (pin "2") (pinfunction "2_2") (pintype "passive"))
      (node (ref "R37") (pin "1") (pinfunction "1_1") (pintype "passive"))
      (node (ref "R51") (pin "1") (pinfunction "1_1") (pintype "passive"))
      (node (ref "R52") (pin "1") (pinfunction "1_1") (pintype "passive"))
      (node (ref "R53") (pin "1") (pinfunction "1_1") (pintype "passive"))
      (node (ref "RJ2") (pin "1") (pinfunction "1_1") (pintype "passive"))
      (node (ref "RS1") (pin "2") (pinfunction "2_2") (pintype "passive"))
      (node (ref "SUN1") (pin "1") (pinfunction "1_1") (pintype "passive"))
      (node (ref "U2") (pin "GND") (pinfunction "GND_GND") (pintype "passive"))
      (node (ref "U3") (pin "GND") (pinfunction "GND_GND") (pintype "passive"))
      (node (ref "U4") (pin "9") (pinfunction "VSS_9") (pintype "passive"))
      (node (ref "U6") (pin "1") (pinfunction "GND_1") (pintype "passive"))
      (node (ref "U7") (pin "5") (pinfunction "VSS_5") (pintype "passive"))
      (node (ref "X1") (pin "2") (pinfunction "GND_2") (pintype "passive"))
      (node (ref "X1") (pin "4") (pinfunction "GND_4") (pintype "passive"))
      (node (ref "Z1") (pin "1") (pinfunction "1_1") (pintype "passive"))
      (node (ref "Z2") (pin "1") (pinfunction "1_1") (pintype "passive"))
    )
    (net (code "51") (name "HBIAS") (class "Default")
      (node (ref "C15") (pin "2") (pinfunction "2_2") (pintype "passive"))
      (node (ref "U4") (pin "11") (pinfunction "HBIAS_11") (pintype "passive"))
    )
    (net (code "52") (name "Net-(ATM1-Pad1)") (class "Default")
      (node (ref "ATM1") (pin "1") (pinfunction "1_1") (pintype "passive"))
      (node (ref "C18") (pin "2") (pinfunction "2_2") (pintype "passive"))
    )
    (net (code "53") (name "Net-(B1-Pad1)") (class "Default")
      (node (ref "B1") (pin "1") (pinfunction "1_1") (pintype "passive"))
      (node (ref "RJ1") (pin "2") (pinfunction "2_2") (pintype "passive"))
    )
    (net (code "54") (name "Net-(C7-Pad1)") (class "Default")
      (node (ref "C7") (pin "1") (pinfunction "1_1") (pintype "passive"))
      (node (ref "R17") (pin "1") (pinfunction "1_1") (pintype "passive"))
      (node (ref "U2") (pin "VIN") (pinfunction "VIN_VIN") (pintype "passive"))
    )
    (net (code "55") (name "Net-(C11-Pad2)") (class "Default")
      (node (ref "C11") (pin "2") (pinfunction "2_2") (pintype "passive"))
      (node (ref "D11") (pin "2") (pinfunction "2_2") (pintype "passive"))
      (node (ref "D12") (pin "2") (pinfunction "2_2") (pintype "passive"))
      (node (ref "R26") (pin "2") (pinfunction "2_2") (pintype "passive"))
      (node (ref "Z2") (pin "2") (pinfunction "2_2") (pintype "passive"))
    )
    (net (code "56") (name "Net-(D11-Pad1)") (class "Default")
      (node (ref "D11") (pin "1") (pinfunction "1_1") (pintype "passive"))
      (node (ref "R25") (pin "2") (pinfunction "2_2") (pintype "passive"))
      (node (ref "R26") (pin "1") (pinfunction "1_1") (pintype "passive"))
    )
    (net (code "57") (name "Net-(D12-Pad1)") (class "Default")
      (node (ref "D12") (pin "1") (pinfunction "1_1") (pintype "passive"))
      (node (ref "Q2") (pin "B") (pinfunction "B_B") (pintype "passive"))
      (node (ref "R22") (pin "1") (pinfunction "1_1") (pintype "passive"))
    )
    (net (code "58") (name "Net-(LED1-Pad1)") (class "Default")
      (node (ref "LED1") (pin "1") (pinfunction "1_1") (pintype "passive"))
      (node (ref "LEDR1") (pin "1") (pinfunction "1_1") (pintype "passive"))
      (node (ref "R49") (pin "2") (pinfunction "2_2") (pintype "passive"))
    )
    (net (code "59") (name "Net-(LED1-Pad3)") (class "Default")
      (node (ref "LED1") (pin "3") (pinfunction "3_3") (pintype "passive"))
      (node (ref "LEDG1") (pin "1") (pinfunction "1_1") (pintype "passive"))
      (node (ref "R50") (pin "2") (pinfunction "2_2") (pintype "passive"))
    )
    (net (code "60") (name "Net-(Q2-PadC)") (class "Default")
      (node (ref "Q2") (pin "C") (pinfunction "C_C") (pintype "passive"))
      (node (ref "R23") (pin "2") (pinfunction "2_2") (pintype "passive"))
    )
    (net (code "61") (name "Net-(Q3-PadG)") (class "Default")
      (node (ref "Q3") (pin "G") (pinfunction "G_G") (pintype "passive"))
      (node (ref "R24") (pin "2") (pinfunction "2_2") (pintype "passive"))
      (node (ref "R27") (pin "2") (pinfunction "2_2") (pintype "passive"))
    )
    (net (code "62") (name "Net-(Q4-G1)") (class "Default")
      (node (ref "Q4") (pin "2") (pinfunction "G1_2") (pintype "passive"))
      (node (ref "R34") (pin "2") (pinfunction "2_2") (pintype "passive"))
    )
    (net (code "63") (name "Net-(Q4-G2)") (class "Default")
      (node (ref "Q4") (pin "4") (pinfunction "G2_4") (pintype "passive"))
      (node (ref "R32") (pin "2") (pinfunction "2_2") (pintype "passive"))
    )
    (net (code "64") (name "Net-(Q5-G1)") (class "Default")
      (node (ref "Q5") (pin "2") (pinfunction "G1_2") (pintype "passive"))
      (node (ref "R38") (pin "2") (pinfunction "2_2") (pintype "passive"))
    )
    (net (code "65") (name "Net-(Q5-G2)") (class "Default")
      (node (ref "Q5") (pin "4") (pinfunction "G2_4") (pintype "passive"))
      (node (ref "R36") (pin "2") (pinfunction "2_2") (pintype "passive"))
    )
    (net (code "66") (name "Net-(Q6-G1)") (class "Default")
      (node (ref "Q6") (pin "2") (pinfunction "G1_2") (pintype "passive"))
      (node (ref "R40") (pin "2") (pinfunction "2_2") (pintype "passive"))
    )
    (net (code "67") (name "Net-(Q6-G2)") (class "Default")
      (node (ref "Q6") (pin "4") (pinfunction "G2_4") (pintype "passive"))
      (node (ref "R39") (pin "2") (pinfunction "2_2") (pintype "passive"))
    )
    (net (code "68") (name "Net-(R29-Pad2)") (class "Default")
      (node (ref "R29") (pin "2") (pinfunction "2_2") (pintype "passive"))
      (node (ref "R30") (pin "1") (pinfunction "1_1") (pintype "passive"))
    )
    (net (code "69") (name "Net-(R30-Pad2)") (class "Default")
      (node (ref "R30") (pin "2") (pinfunction "2_2") (pintype "passive"))
      (node (ref "R31") (pin "1") (pinfunction "1_1") (pintype "passive"))
    )
    (net (code "70") (name "Net-(U4-DIR)") (class "Default")
      (node (ref "R33") (pin "2") (pinfunction "2_2") (pintype "passive"))
      (node (ref "U4") (pin "23") (pinfunction "DIR_23") (pintype "passive"))
    )
    (net (code "71") (name "Net-(U7-IO7)") (class "Default")
      (node (ref "R43") (pin "2") (pinfunction "2_2") (pintype "passive"))
      (node (ref "U7") (pin "12") (pinfunction "IO7_12") (pintype "passive"))
    )
    (net (code "72") (name "Net-(U7-RF)") (class "Default")
      (node (ref "C18") (pin "1") (pinfunction "1_1") (pintype "passive"))
      (node (ref "U7") (pin "4") (pinfunction "RF_4") (pintype "passive"))
    )
    (net (code "73") (name "Net-(U7-VIN)") (class "Default")
      (node (ref "C21") (pin "2") (pinfunction "2_2") (pintype "passive"))
      (node (ref "Q7") (pin "D") (pinfunction "D_D") (pintype "passive"))
      (node (ref "U7") (pin "10") (pinfunction "VIN_10") (pintype "passive"))
    )
    (net (code "74") (name "SUN") (class "Default")
      (node (ref "D7") (pin "1") (pinfunction "1_1") (pintype "passive"))
      (node (ref "D8") (pin "1") (pinfunction "1_1") (pintype "passive"))
      (node (ref "R19") (pin "2") (pinfunction "2_2") (pintype "passive"))
      (node (ref "R20") (pin "2") (pinfunction "2_2") (pintype "passive"))
      (node (ref "SUN1") (pin "2") (pinfunction "2_2") (pintype "passive"))
    )
    (net (code "75") (name "VDD5") (class "Default")
      (node (ref "C16") (pin "2") (pinfunction "2_2") (pintype "passive"))
      (node (ref "J3") (pin "1") (pinfunction "1_1") (pintype "passive"))
      (node (ref "U4") (pin "10") (pinfunction "VDD5_10") (pintype "passive"))
      (node (ref "VDD1") (pin "1") (pinfunction "1_1") (pintype "passive"))
    )
    (net (code "76") (name "unconnected-(MARK1-Pad1)") (class "Default")
      (node (ref "MARK1") (pin "1") (pinfunction "1_1") (pintype "passive"))
    )
    (net (code "77") (name "unconnected-(MARK2-Pad1)") (class "Default")
      (node (ref "MARK2") (pin "1") (pinfunction "1_1") (pintype "passive"))
    )
    (net (code "78") (name "unconnected-(U4-A0M-Pad19)") (class "Default")
      (node (ref "U4") (pin "19") (pinfunction "A0M_19") (pintype "passive"))
    )
    (net (code "79") (name "unconnected-(U4-A0P-Pad20)") (class "Default")
      (node (ref "U4") (pin "20") (pinfunction "A0P_20") (pintype "passive"))
    )
    (net (code "80") (name "unconnected-(U4-ASPEED-Pad22)") (class "Default")
      (node (ref "U4") (pin "22") (pinfunction "ASPEED_22") (pintype "passive"))
    )
    (net (code "81") (name "unconnected-(U6-CLKO{slash}TIM1_CH2N{slash}TIM1_CH4{slash}AN0{slash}PB1-Pad6)") (class "Default")
      (node (ref "U6") (pin "6") (pinfunction "CLKO/TIM1_CH2N/TIM1_CH4/AN0/PB1_6") (pintype "passive"))
    )
    (net (code "82") (name "unconnected-(U6-PB7{slash}OSC2{slash}ELVD3-Pad18)") (class "Default")
      (node (ref "U6") (pin "18") (pinfunction "PB7/OSC2/ELVD3_18") (pintype "passive"))
    )
    (net (code "83") (name "unconnected-(U7-IIO6-Pad13)") (class "Default")
      (node (ref "U7") (pin "13") (pinfunction "IIO6_13") (pintype "passive"))
    )
    (net (code "84") (name "unconnected-(U7-IO5-Pad14)") (class "Default")
      (node (ref "U7") (pin "14") (pinfunction "IO5_14") (pintype "passive"))
    )
    (net (code "85") (name "unconnected-(U7-IO8-Pad11)") (class "Default")
      (node (ref "U7") (pin "11") (pinfunction "IO8_11") (pintype "passive"))
    )
    (net (code "86") (name "unconnected-(U7-IO10-Pad6)") (class "Default")
      (node (ref "U7") (pin "6") (pinfunction "IO10_6") (pintype "passive"))
    )
    (net (code "87") (name "unconnected-(U7-IO11-Pad7)") (class "Default")
      (node (ref "U7") (pin "7") (pinfunction "IO11_7") (pintype "passive"))
    )
    (net (code "88") (name "unconnected-(U7-IO12-Pad8)") (class "Default")
      (node (ref "U7") (pin "8") (pinfunction "IO12_8") (pintype "passive"))
    )
    (net (code "89") (name "unconnected-(U7-IO13-Pad9)") (class "Default")
      (node (ref "U7") (pin "9") (pinfunction "IO13_9") (pintype "passive"))
    )
    (net (code "90") (name "unconnected-(U7-NC-Pad1)") (class "Default")
      (node (ref "U7") (pin "1") (pinfunction "NC_1") (pintype "passive"))
    )
  )
)
